# vtg_regulator_using_TPS793.net
KiCad netlist of a schematic drawn in Altium Designer
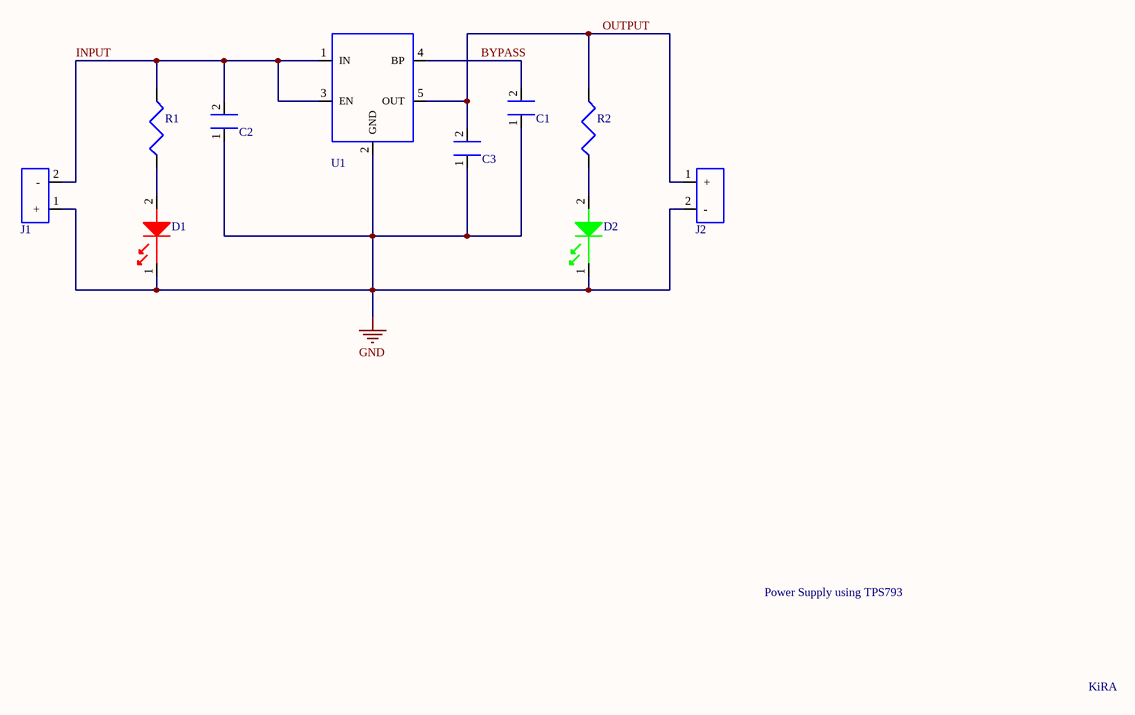
[diagram p0: vtg regulator using TPS793.SchDoc]

(export (version "E")
  (design (tool "Eeschema 10.0.6"))
  (components
    (comp (ref "C1")
      (value "Capacitor 0805 0.01uF")
      (footprint "Capacitor 0805 0.01uF")
      (fields (field (name "MANUFACTURER") "Vishay") (field (name "PART NO") "VJ0805Y103KXAAC"))
      (libsource (lib "Pwr sup TPS793") (part "Capacitor 0805 0.01uF"))
    )
    (comp (ref "C2")
      (value "Capacitor 0805 0.1uF")
      (footprint "Capacitor 0805 0.1uF")
      (fields (field (name "MANUFACTURER") "Vishay") (field (name "PART NO") "VJ0805Y104KXAAT"))
      (libsource (lib "Pwr sup TPS793") (part "Capacitor 0805 0.1uF"))
    )
    (comp (ref "C3")
      (value "Capacitor 0805 2.2uF")
      (footprint "Capacitor 0805 2.2uF")
      (fields (field (name "MANUFACTURER") "Vishay") (field (name "PART NO") "VJ0805V225MXQTW1BC"))
      (libsource (lib "Pwr sup TPS793") (part "Capacitor 0805 2.2uF"))
    )
    (comp (ref "D1")
      (value "LED 0805 Red")
      (footprint "LED 0805 Red")
      (fields (field (name "MANUFACTURER") "Lite-On Inc") (field (name "PART NO") "LTST-C171KRKT"))
      (libsource (lib "Pwr sup TPS793") (part "LED 0805 Red"))
    )
    (comp (ref "D2")
      (value "LED 0805 Green")
      (footprint "LED 0805 Green")
      (fields (field (name "MANUFACTURER") "Lite-On Inc") (field (name "PART NO") "LTST-C171GKT"))
      (libsource (lib "Pwr sup TPS793") (part "LED 0805 Green"))
    )
    (comp (ref "J1")
      (value "Generic Header, 1X2 Vertical")
      (footprint "22232021")
      (fields (field (name "MANUFACTURER") "Molex") (field (name "PART NO") "22232021"))
      (libsource (lib "Pwr sup TPS793") (part "22232021"))
    )
    (comp (ref "J2")
      (value "Generic Header, 1X2 Vertical")
      (footprint "22232021")
      (fields (field (name "MANUFACTURER") "Molex") (field (name "PART NO") "22232021"))
      (libsource (lib "Pwr sup TPS793") (part "22232021"))
    )
    (comp (ref "R1")
      (value "Resistor 0805 291R")
      (footprint "Resistor 0805 291R")
      (fields
        (field (name "MANUFACTURER") "KOA Speer Electronics Inc")
        (field (name "PART NO") "(RN73R2ATTD2910B25)")
        (field (name "TOLERANCE") "0.1%")
      )
      (libsource (lib "Pwr sup TPS793") (part "Resistor 0805 291R"))
    )
    (comp (ref "R2")
      (value "Resistor 0805 300R")
      (footprint "Resistor 0805 300R")
      (fields (field (name "MANUFACTURER") "YAGEO") (field (name "PART NO") "RC0805JR-07300RL"))
      (libsource (lib "Pwr sup TPS793") (part "Resistor 0805 300R"))
    )
    (comp (ref "U1")
      (value "TPS793")
      (footprint "TPS793")
      (fields (field (name "MANUFACTURER") "Texas Instrument") (field (name "PART NO") "TPS79333DBVRQ1"))
      (libsource (lib "Pwr sup TPS793") (part "Regulator TPS793"))
    )
  )
  (nets
    (net (code "1") (name "/BYPASS") (class "Default")
      (node (ref "C1") (pin "2") (pinfunction "2_2") (pintype "passive"))
      (node (ref "U1") (pin "4") (pinfunction "BP_4") (pintype "passive"))
    )
    (net (code "2") (name "/INPUT") (class "Default")
      (node (ref "C2") (pin "2") (pinfunction "2_2") (pintype "passive"))
      (node (ref "J1") (pin "2") (pinfunction "-_2") (pintype "passive"))
      (node (ref "R1") (pin "2") (pinfunction "2_2") (pintype "passive"))
      (node (ref "U1") (pin "1") (pinfunction "IN_1") (pintype "passive"))
      (node (ref "U1") (pin "3") (pinfunction "EN_3") (pintype "passive"))
    )
    (net (code "3") (name "/OUTPUT") (class "Default")
      (node (ref "C3") (pin "2") (pinfunction "2_2") (pintype "passive"))
      (node (ref "J2") (pin "1") (pinfunction "+_1") (pintype "passive"))
      (node (ref "R2") (pin "2") (pinfunction "2_2") (pintype "passive"))
      (node (ref "U1") (pin "5") (pinfunction "OUT_5") (pintype "passive"))
    )
    (net (code "4") (name "GND") (class "Default")
      (node (ref "C1") (pin "1") (pinfunction "1_1") (pintype "passive"))
      (node (ref "C2") (pin "1") (pinfunction "1_1") (pintype "passive"))
      (node (ref "C3") (pin "1") (pinfunction "1_1") (pintype "passive"))
      (node (ref "D1") (pin "1") (pinfunction "1_1") (pintype "passive"))
      (node (ref "D2") (pin "1") (pinfunction "1_1") (pintype "passive"))
      (node (ref "J1") (pin "1") (pinfunction "+_1") (pintype "passive"))
      (node (ref "J2") (pin "2") (pinfunction "-_2") (pintype "passive"))
      (node (ref "U1") (pin "2") (pinfunction "GND_2") (pintype "passive"))
    )
    (net (code "5") (name "Net-(D1-Pad2)") (class "Default")
      (node (ref "D1") (pin "2") (pinfunction "2_2") (pintype "passive"))
      (node (ref "R1") (pin "1") (pinfunction "1_1") (pintype "passive"))
    )
    (net (code "6") (name "Net-(D2-Pad2)") (class "Default")
      (node (ref "D2") (pin "2") (pinfunction "2_2") (pintype "passive"))
      (node (ref "R2") (pin "1") (pinfunction "1_1") (pintype "passive"))
    )
  )
)
